# SparkFun_AS3935_Lightning_Detector.net
KiCad netlist of a schematic drawn in EAGLE
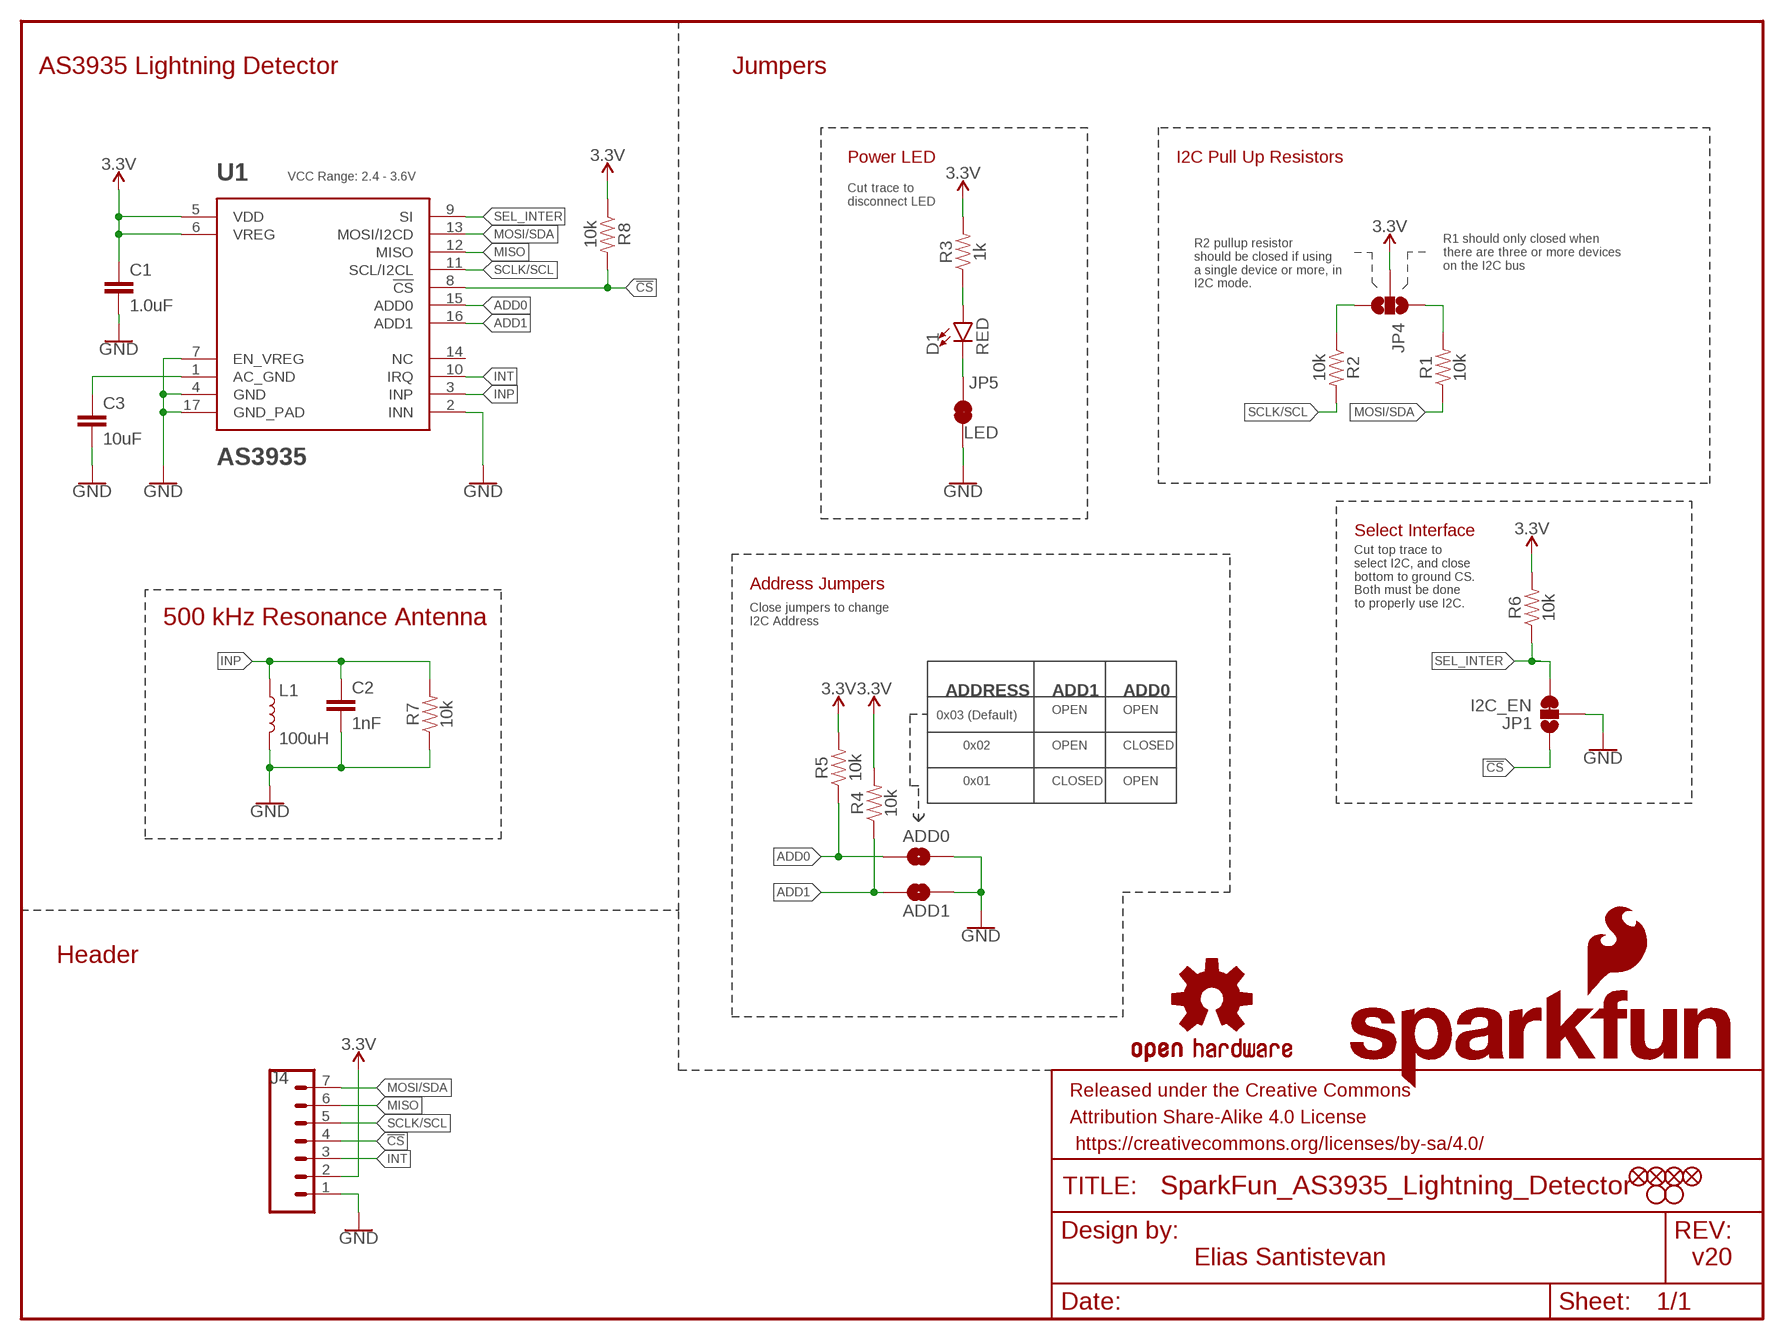
[diagram p0: schematic, sheet 1]

(export (version "E")
  (design (tool "Eeschema 10.0.6"))
  (components
    (comp (ref "ADD0")
      (value "JUMPER-SMT_2_NO_SILK")
      (footprint "eagle-import:SMT-JUMPER_2_NO_SILK")
      (libsource (lib "eagle-import") (part "JUMPER-SMT_2_NO_SILK"))
    )
    (comp (ref "ADD1")
      (value "JUMPER-SMT_2_NO_SILK")
      (footprint "eagle-import:SMT-JUMPER_2_NO_SILK")
      (libsource (lib "eagle-import") (part "JUMPER-SMT_2_NO_SILK"))
    )
    (comp (ref "C1")
      (value "1.0uF")
      (footprint "eagle-import:0603")
      (libsource (lib "eagle-import") (part "1.0UF-0603-16V-10%"))
    )
    (comp (ref "C2")
      (value "1nF")
      (footprint "eagle-import:0603")
      (libsource (lib "eagle-import") (part "1.0NF/1000PF-0603-50V-10%"))
    )
    (comp (ref "C3")
      (value "10uF")
      (footprint "eagle-import:0603")
      (libsource (lib "eagle-import") (part "10UF-0603-6.3V-20%"))
    )
    (comp (ref "D1")
      (value "RED")
      (footprint "eagle-import:LED-0603")
      (libsource (lib "eagle-import") (part "LED-RED0603"))
    )
    (comp (ref "FD1")
      (value "FIDUCIAL1X2")
      (footprint "eagle-import:FIDUCIAL-1X2")
      (libsource (lib "eagle-import") (part "FIDUCIAL1X2"))
    )
    (comp (ref "FD2")
      (value "FIDUCIAL1X2")
      (footprint "eagle-import:FIDUCIAL-1X2")
      (libsource (lib "eagle-import") (part "FIDUCIAL1X2"))
    )
    (comp (ref "FD3")
      (value "FIDUCIAL1X2")
      (footprint "eagle-import:FIDUCIAL-1X2")
      (libsource (lib "eagle-import") (part "FIDUCIAL1X2"))
    )
    (comp (ref "FD4")
      (value "FIDUCIAL1X2")
      (footprint "eagle-import:FIDUCIAL-1X2")
      (libsource (lib "eagle-import") (part "FIDUCIAL1X2"))
    )
    (comp (ref "FRAME1")
      (value "FRAME-LETTER")
      (footprint "eagle-import:CREATIVE_COMMONS")
      (libsource (lib "eagle-import") (part "FRAME-LETTER"))
    )
    (comp (ref "H1")
      (value "STAND-OFFTIGHT")
      (footprint "eagle-import:STAND-OFF-TIGHT")
      (libsource (lib "eagle-import") (part "STAND-OFFTIGHT"))
    )
    (comp (ref "H2")
      (value "STAND-OFFTIGHT")
      (footprint "eagle-import:STAND-OFF-TIGHT")
      (libsource (lib "eagle-import") (part "STAND-OFFTIGHT"))
    )
    (comp (ref "J4")
      (value "CONN_07NO_SILK")
      (footprint "eagle-import:1X07_NO_SILK")
      (libsource (lib "eagle-import") (part "CONN_07NO_SILK"))
    )
    (comp (ref "JP1")
      (value "I2C_EN")
      (footprint "eagle-import:SMT-JUMPER_3_1-NC_TRACE_SILK")
      (libsource (lib "eagle-import") (part "JUMPER-SMT_3_1-NC_TRACE_SILK"))
    )
    (comp (ref "JP4")
      (value "JUMPER-SMT_3_NO_SILK")
      (footprint "eagle-import:SMT-JUMPER_3_NO_SILK")
      (libsource (lib "eagle-import") (part "JUMPER-SMT_3_NO_SILK"))
    )
    (comp (ref "JP5")
      (value "LED")
      (footprint "eagle-import:SMT-JUMPER_2_NC_TRACE_SILK")
      (libsource (lib "eagle-import") (part "JUMPER-SMT_2_NC_TRACE_SILK"))
    )
    (comp (ref "L1")
      (value "100uH")
      (footprint "eagle-import:MA5532-AE")
      (libsource (lib "eagle-import") (part "MA5532-AE"))
    )
    (comp (ref "LOGO1")
      (value "OSHW-LOGOS")
      (footprint "eagle-import:OSHW-LOGO-S")
      (libsource (lib "eagle-import") (part "OSHW-LOGOS"))
    )
    (comp (ref "LOGO2")
      (value "SFE_LOGO_NAME.1_INCH")
      (footprint "eagle-import:SFE_LOGO_NAME_.1")
      (libsource (lib "eagle-import") (part "SFE_LOGO_NAME.1_INCH"))
    )
    (comp (ref "LOGO3")
      (value "SFE_LOGO_FLAME.2_INCH")
      (footprint "eagle-import:SFE_LOGO_FLAME_.2")
      (libsource (lib "eagle-import") (part "SFE_LOGO_FLAME.2_INCH"))
    )
    (comp (ref "R1")
      (value "10k")
      (footprint "eagle-import:0603")
      (libsource (lib "eagle-import") (part "10KOHM-0603-1/10W-1%"))
    )
    (comp (ref "R2")
      (value "10k")
      (footprint "eagle-import:0603")
      (libsource (lib "eagle-import") (part "10KOHM-0603-1/10W-1%"))
    )
    (comp (ref "R3")
      (value "1k")
      (footprint "eagle-import:0603")
      (libsource (lib "eagle-import") (part "1KOHM-0603-1/10W-1%"))
    )
    (comp (ref "R4")
      (value "10k")
      (footprint "eagle-import:0603")
      (libsource (lib "eagle-import") (part "10KOHM-0603-1/10W-1%"))
    )
    (comp (ref "R5")
      (value "10k")
      (footprint "eagle-import:0603")
      (libsource (lib "eagle-import") (part "10KOHM-0603-1/10W-1%"))
    )
    (comp (ref "R6")
      (value "10k")
      (footprint "eagle-import:0603")
      (libsource (lib "eagle-import") (part "10KOHM-0603-1/10W-1%"))
    )
    (comp (ref "R7")
      (value "10k")
      (footprint "eagle-import:0603")
      (libsource (lib "eagle-import") (part "10KOHM-0603-1/10W-1%"))
    )
    (comp (ref "R8")
      (value "10k")
      (footprint "eagle-import:0603")
      (libsource (lib "eagle-import") (part "10KOHM-0603-1/10W-1%"))
    )
    (comp (ref "U1")
      (value "AS3935")
      (footprint "eagle-import:16LD_MLPQ")
      (libsource (lib "eagle-import") (part "AS3935QFN"))
    )
  )
  (nets
    (net (code "1") (name "/~{CS}") (class "Default")
      (node (ref "J4") (pin "4") (pinfunction "4_4") (pintype "passive"))
      (node (ref "JP1") (pin "1") (pinfunction "1_1") (pintype "passive"))
      (node (ref "R8") (pin "2") (pinfunction "2_2") (pintype "passive"))
      (node (ref "U1") (pin "8") (pinfunction "~{CS}_8") (pintype "input"))
    )
    (net (code "2") (name "3.3V") (class "Default")
      (node (ref "C1") (pin "1") (pinfunction "1_1") (pintype "passive"))
      (node (ref "J4") (pin "2") (pinfunction "2_2") (pintype "passive"))
      (node (ref "JP4") (pin "2") (pinfunction "2_2") (pintype "passive"))
      (node (ref "R3") (pin "2") (pinfunction "2_2") (pintype "passive"))
      (node (ref "R4") (pin "2") (pinfunction "2_2") (pintype "passive"))
      (node (ref "R5") (pin "2") (pinfunction "2_2") (pintype "passive"))
      (node (ref "R6") (pin "2") (pinfunction "2_2") (pintype "passive"))
      (node (ref "R8") (pin "1") (pinfunction "1_1") (pintype "passive"))
      (node (ref "U1") (pin "5") (pinfunction "VDD_5") (pintype "power_in"))
      (node (ref "U1") (pin "6") (pinfunction "VREG_6") (pintype "power_in"))
    )
    (net (code "3") (name "ADD0") (class "Default")
      (node (ref "ADD0") (pin "1") (pinfunction "1_1") (pintype "passive"))
      (node (ref "R5") (pin "1") (pinfunction "1_1") (pintype "passive"))
      (node (ref "U1") (pin "15") (pinfunction "ADD0_15") (pintype "input"))
    )
    (net (code "4") (name "ADD1") (class "Default")
      (node (ref "ADD1") (pin "1") (pinfunction "1_1") (pintype "passive"))
      (node (ref "R4") (pin "1") (pinfunction "1_1") (pintype "passive"))
      (node (ref "U1") (pin "16") (pinfunction "ADD1_16") (pintype "input"))
    )
    (net (code "5") (name "GND") (class "Default")
      (node (ref "ADD0") (pin "2") (pinfunction "2_2") (pintype "passive"))
      (node (ref "ADD1") (pin "2") (pinfunction "2_2") (pintype "passive"))
      (node (ref "C1") (pin "2") (pinfunction "2_2") (pintype "passive"))
      (node (ref "C2") (pin "2") (pinfunction "2_2") (pintype "passive"))
      (node (ref "C3") (pin "2") (pinfunction "2_2") (pintype "passive"))
      (node (ref "J4") (pin "1") (pinfunction "1_1") (pintype "passive"))
      (node (ref "JP1") (pin "2") (pinfunction "2_2") (pintype "passive"))
      (node (ref "JP5") (pin "1") (pinfunction "1_1") (pintype "passive"))
      (node (ref "L1") (pin "2") (pinfunction "2_2") (pintype "passive"))
      (node (ref "R7") (pin "1") (pinfunction "1_1") (pintype "passive"))
      (node (ref "U1") (pin "17") (pinfunction "GND_PAD_17") (pintype "power_in"))
      (node (ref "U1") (pin "2") (pinfunction "INN_2") (pintype "bidirectional"))
      (node (ref "U1") (pin "4") (pinfunction "GND_4") (pintype "power_in"))
      (node (ref "U1") (pin "7") (pinfunction "EN_VREG_7") (pintype "bidirectional"))
    )
    (net (code "6") (name "INP") (class "Default")
      (node (ref "C2") (pin "1") (pinfunction "1_1") (pintype "passive"))
      (node (ref "L1") (pin "1") (pinfunction "1_1") (pintype "passive"))
      (node (ref "R7") (pin "2") (pinfunction "2_2") (pintype "passive"))
      (node (ref "U1") (pin "3") (pinfunction "INP_3") (pintype "bidirectional"))
    )
    (net (code "7") (name "INT") (class "Default")
      (node (ref "J4") (pin "3") (pinfunction "3_3") (pintype "passive"))
      (node (ref "U1") (pin "10") (pinfunction "IRQ_10") (pintype "bidirectional"))
    )
    (net (code "8") (name "MISO") (class "Default")
      (node (ref "J4") (pin "6") (pinfunction "6_6") (pintype "passive"))
      (node (ref "U1") (pin "12") (pinfunction "MISO_12") (pintype "output"))
    )
    (net (code "9") (name "MOSI{slash}SDA") (class "Default")
      (node (ref "J4") (pin "7") (pinfunction "7_7") (pintype "passive"))
      (node (ref "R1") (pin "1") (pinfunction "1_1") (pintype "passive"))
      (node (ref "U1") (pin "13") (pinfunction "MOSI/I2CD_13") (pintype "input"))
    )
    (net (code "10") (name "Net-(D1-PadA)") (class "Default")
      (node (ref "D1") (pin "A") (pinfunction "A_A") (pintype "passive"))
      (node (ref "R3") (pin "1") (pinfunction "1_1") (pintype "passive"))
    )
    (net (code "11") (name "Net-(D1-PadC)") (class "Default")
      (node (ref "D1") (pin "C") (pinfunction "C_C") (pintype "passive"))
      (node (ref "JP5") (pin "2") (pinfunction "2_2") (pintype "passive"))
    )
    (net (code "12") (name "Net-(JP4-Pad1)") (class "Default")
      (node (ref "JP4") (pin "1") (pinfunction "1_1") (pintype "passive"))
      (node (ref "R1") (pin "2") (pinfunction "2_2") (pintype "passive"))
    )
    (net (code "13") (name "Net-(JP4-Pad3)") (class "Default")
      (node (ref "JP4") (pin "3") (pinfunction "3_3") (pintype "passive"))
      (node (ref "R2") (pin "1") (pinfunction "1_1") (pintype "passive"))
    )
    (net (code "14") (name "Net-(U1-AC_GND)") (class "Default")
      (node (ref "C3") (pin "1") (pinfunction "1_1") (pintype "passive"))
      (node (ref "U1") (pin "1") (pinfunction "AC_GND_1") (pintype "power_in"))
    )
    (net (code "15") (name "SCLK{slash}SCL") (class "Default")
      (node (ref "J4") (pin "5") (pinfunction "5_5") (pintype "passive"))
      (node (ref "R2") (pin "2") (pinfunction "2_2") (pintype "passive"))
      (node (ref "U1") (pin "11") (pinfunction "SCL/I2CL_11") (pintype "input"))
    )
    (net (code "16") (name "SEL_INTER") (class "Default")
      (node (ref "JP1") (pin "3") (pinfunction "3_3") (pintype "passive"))
      (node (ref "R6") (pin "1") (pinfunction "1_1") (pintype "passive"))
      (node (ref "U1") (pin "9") (pinfunction "SI_9") (pintype "input"))
    )
    (net (code "17") (name "unconnected-(U1-NC-Pad14)") (class "Default")
      (node (ref "U1") (pin "14") (pinfunction "NC_14") (pintype "no_connect"))
    )
  )
)
